# Motortreiber_1_2.net
KiCad netlist of a schematic drawn in Altium Designer
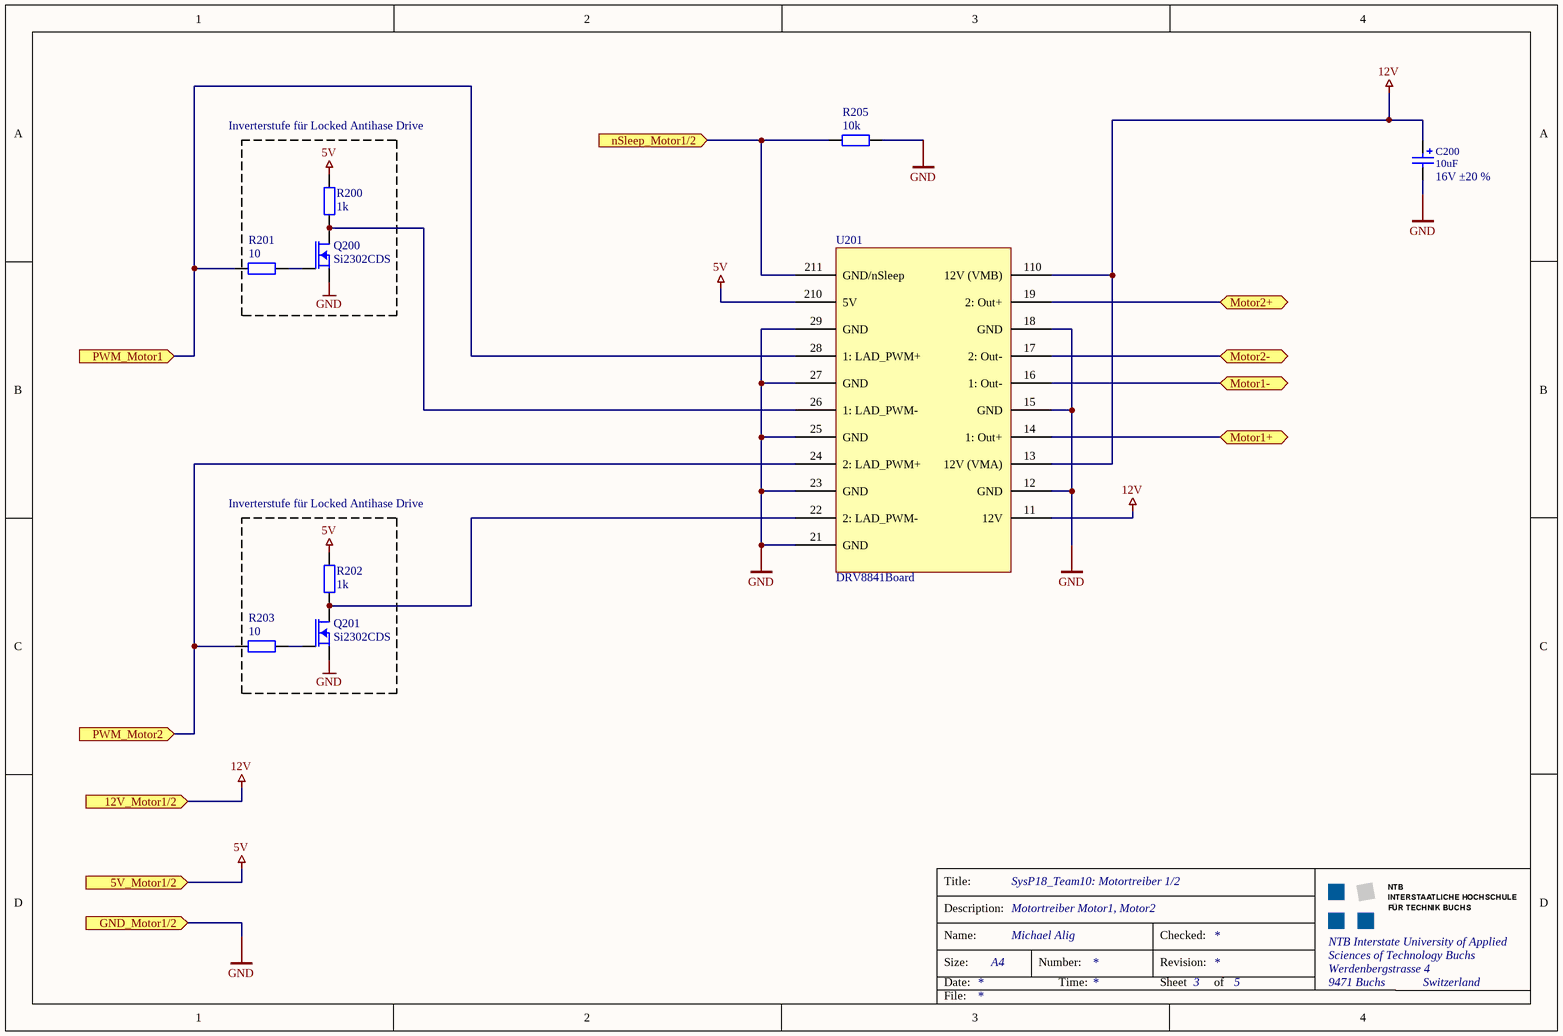
[diagram p0: Motortreiber_1,2.SchDoc]

(export (version "E")
  (design (tool "Eeschema 10.0.6"))
  (components
    (comp (ref "C200")
      (value "10uF")
      (footprint "CDE_CAP AVE CODE D_H")
      (description "Aluminum Electrolytic Capacitors for Filtering and Bypass, 47uF, 16V")
      (fields
        (field (name "MANUFACTURER") "Cornell Dubilier")
        (field (name "VALUEADDON") "16V ±20 %")
        (field (name "Comment") "AVE476M16D16T-F")
        (field (name "PUBLISHER") "Stefan Ursella, M.Eng")
      )
      (libsource (lib "Motorentreiber") (part "CDE_AVE476M16D16T-F_AVE CODE D"))
    )
    (comp (ref "Q200")
      (value "Si2302CDS")
      (footprint "SOT23-3")
      (description "N-Channel 20V (D-S) MOSFET")
      (libsource (lib "Motorentreiber") (part "Depletion Mode MOSFET"))
    )
    (comp (ref "Q201")
      (value "Si2302CDS")
      (footprint "SOT23-3")
      (description "N-Channel 20V (D-S) MOSFET")
      (libsource (lib "Motorentreiber") (part "Depletion Mode MOSFET"))
    )
    (comp (ref "R200")
      (value "1k")
      (footprint "GEN_R0805_H")
      (description "generic resistor")
      (fields
        (field (name "MANUFACTURER") "Tbd")
        (field (name "Comment") "Generic")
        (field (name "PUBLISHER") "Altium Limited")
      )
      (libsource (lib "") (part "GEN_R_2_1"))
    )
    (comp (ref "R201")
      (value "10")
      (footprint "GEN_R0805_H")
      (description "generic resistor")
      (fields
        (field (name "MANUFACTURER") "Tbd")
        (field (name "Comment") "Generic")
        (field (name "PUBLISHER") "Altium Limited")
      )
      (libsource (lib "Motorentreiber") (part "GEN_R_2"))
    )
    (comp (ref "R202")
      (value "1k")
      (footprint "GEN_R0805_H")
      (description "generic resistor")
      (fields
        (field (name "MANUFACTURER") "Tbd")
        (field (name "Comment") "Generic")
        (field (name "PUBLISHER") "Altium Limited")
      )
      (libsource (lib "") (part "GEN_R_2_1"))
    )
    (comp (ref "R203")
      (value "10")
      (footprint "GEN_R0805_H")
      (description "generic resistor")
      (fields
        (field (name "MANUFACTURER") "Tbd")
        (field (name "Comment") "Generic")
        (field (name "PUBLISHER") "Altium Limited")
      )
      (libsource (lib "Motorentreiber") (part "GEN_R_2"))
    )
    (comp (ref "R205")
      (value "10k")
      (footprint "GEN_R0805_H")
      (description "generic resistor")
      (fields
        (field (name "MANUFACTURER") "Tbd")
        (field (name "Comment") "Generic")
        (field (name "PUBLISHER") "Altium Limited")
      )
      (libsource (lib "Motorentreiber") (part "GEN_R_2"))
    )
    (comp (ref "U201")
      (value "DRV8841Board")
      (footprint "DRV8841_Board")
      (libsource (lib "Motorentreiber") (part "DRV8841_Board"))
    )
  )
  (nets
    (net (code "1") (name "/Motor1+") (class "Default")
      (node (ref "U201") (pin "14") (pinfunction "1:_Out+_14") (pintype "passive"))
    )
    (net (code "2") (name "/Motor1-") (class "Default")
      (node (ref "U201") (pin "16") (pinfunction "1:_Out-_16") (pintype "passive"))
    )
    (net (code "3") (name "/Motor2+") (class "Default")
      (node (ref "U201") (pin "19") (pinfunction "2:_Out+_19") (pintype "passive"))
    )
    (net (code "4") (name "/Motor2-") (class "Default")
      (node (ref "U201") (pin "17") (pinfunction "2:_Out-_17") (pintype "passive"))
    )
    (net (code "5") (name "/PWM_Motor1") (class "Default")
      (node (ref "R201") (pin "1") (pinfunction "1_1") (pintype "passive"))
      (node (ref "U201") (pin "28") (pinfunction "1:_LAD_PWM+_28") (pintype "passive"))
    )
    (net (code "6") (name "/PWM_Motor2") (class "Default")
      (node (ref "R203") (pin "1") (pinfunction "1_1") (pintype "passive"))
      (node (ref "U201") (pin "24") (pinfunction "2:_LAD_PWM+_24") (pintype "passive"))
    )
    (net (code "7") (name "/nSleep_Motor1{slash}2") (class "Default")
      (node (ref "R205") (pin "1") (pinfunction "1_1") (pintype "passive"))
      (node (ref "U201") (pin "211") (pinfunction "GND/nSleep_211") (pintype "passive"))
    )
    (net (code "8") (name "5V") (class "Default")
      (node (ref "R200") (pin "2") (pinfunction "2_2") (pintype "passive"))
      (node (ref "R202") (pin "2") (pinfunction "2_2") (pintype "passive"))
      (node (ref "U201") (pin "210") (pinfunction "5V_210") (pintype "passive"))
    )
    (net (code "9") (name "12V") (class "Default")
      (node (ref "C200") (pin "1") (pinfunction "Pos_1") (pintype "passive"))
      (node (ref "U201") (pin "11") (pinfunction "12V_11") (pintype "passive"))
      (node (ref "U201") (pin "110") (pinfunction "12V_(VMB)_110") (pintype "passive"))
      (node (ref "U201") (pin "13") (pinfunction "12V_(VMA)_13") (pintype "passive"))
    )
    (net (code "10") (name "GND") (class "Default")
      (node (ref "C200") (pin "2") (pinfunction "Neg_2") (pintype "passive"))
      (node (ref "Q200") (pin "2") (pinfunction "S_2") (pintype "passive"))
      (node (ref "Q201") (pin "2") (pinfunction "S_2") (pintype "passive"))
      (node (ref "R205") (pin "2") (pinfunction "2_2") (pintype "passive"))
      (node (ref "U201") (pin "12") (pinfunction "GND_12") (pintype "passive"))
      (node (ref "U201") (pin "15") (pinfunction "GND_15") (pintype "passive"))
      (node (ref "U201") (pin "18") (pinfunction "GND_18") (pintype "passive"))
      (node (ref "U201") (pin "21") (pinfunction "GND_21") (pintype "passive"))
      (node (ref "U201") (pin "23") (pinfunction "GND_23") (pintype "passive"))
      (node (ref "U201") (pin "25") (pinfunction "GND_25") (pintype "passive"))
      (node (ref "U201") (pin "27") (pinfunction "GND_27") (pintype "passive"))
      (node (ref "U201") (pin "29") (pinfunction "GND_29") (pintype "passive"))
    )
    (net (code "11") (name "Net-(Q200-D)") (class "Default")
      (node (ref "Q200") (pin "3") (pinfunction "D_3") (pintype "passive"))
      (node (ref "R200") (pin "1") (pinfunction "1_1") (pintype "passive"))
      (node (ref "U201") (pin "26") (pinfunction "1:_LAD_PWM-_26") (pintype "passive"))
    )
    (net (code "12") (name "Net-(Q200-G)") (class "Default")
      (node (ref "Q200") (pin "1") (pinfunction "G_1") (pintype "passive"))
      (node (ref "R201") (pin "2") (pinfunction "2_2") (pintype "passive"))
    )
    (net (code "13") (name "Net-(Q201-D)") (class "Default")
      (node (ref "Q201") (pin "3") (pinfunction "D_3") (pintype "passive"))
      (node (ref "R202") (pin "1") (pinfunction "1_1") (pintype "passive"))
      (node (ref "U201") (pin "22") (pinfunction "2:_LAD_PWM-_22") (pintype "passive"))
    )
    (net (code "14") (name "Net-(Q201-G)") (class "Default")
      (node (ref "Q201") (pin "1") (pinfunction "G_1") (pintype "passive"))
      (node (ref "R203") (pin "2") (pinfunction "2_2") (pintype "passive"))
    )
  )
)
